# MapleIoT_P2_V1_0.net
KiCad netlist of a schematic drawn in EAGLE
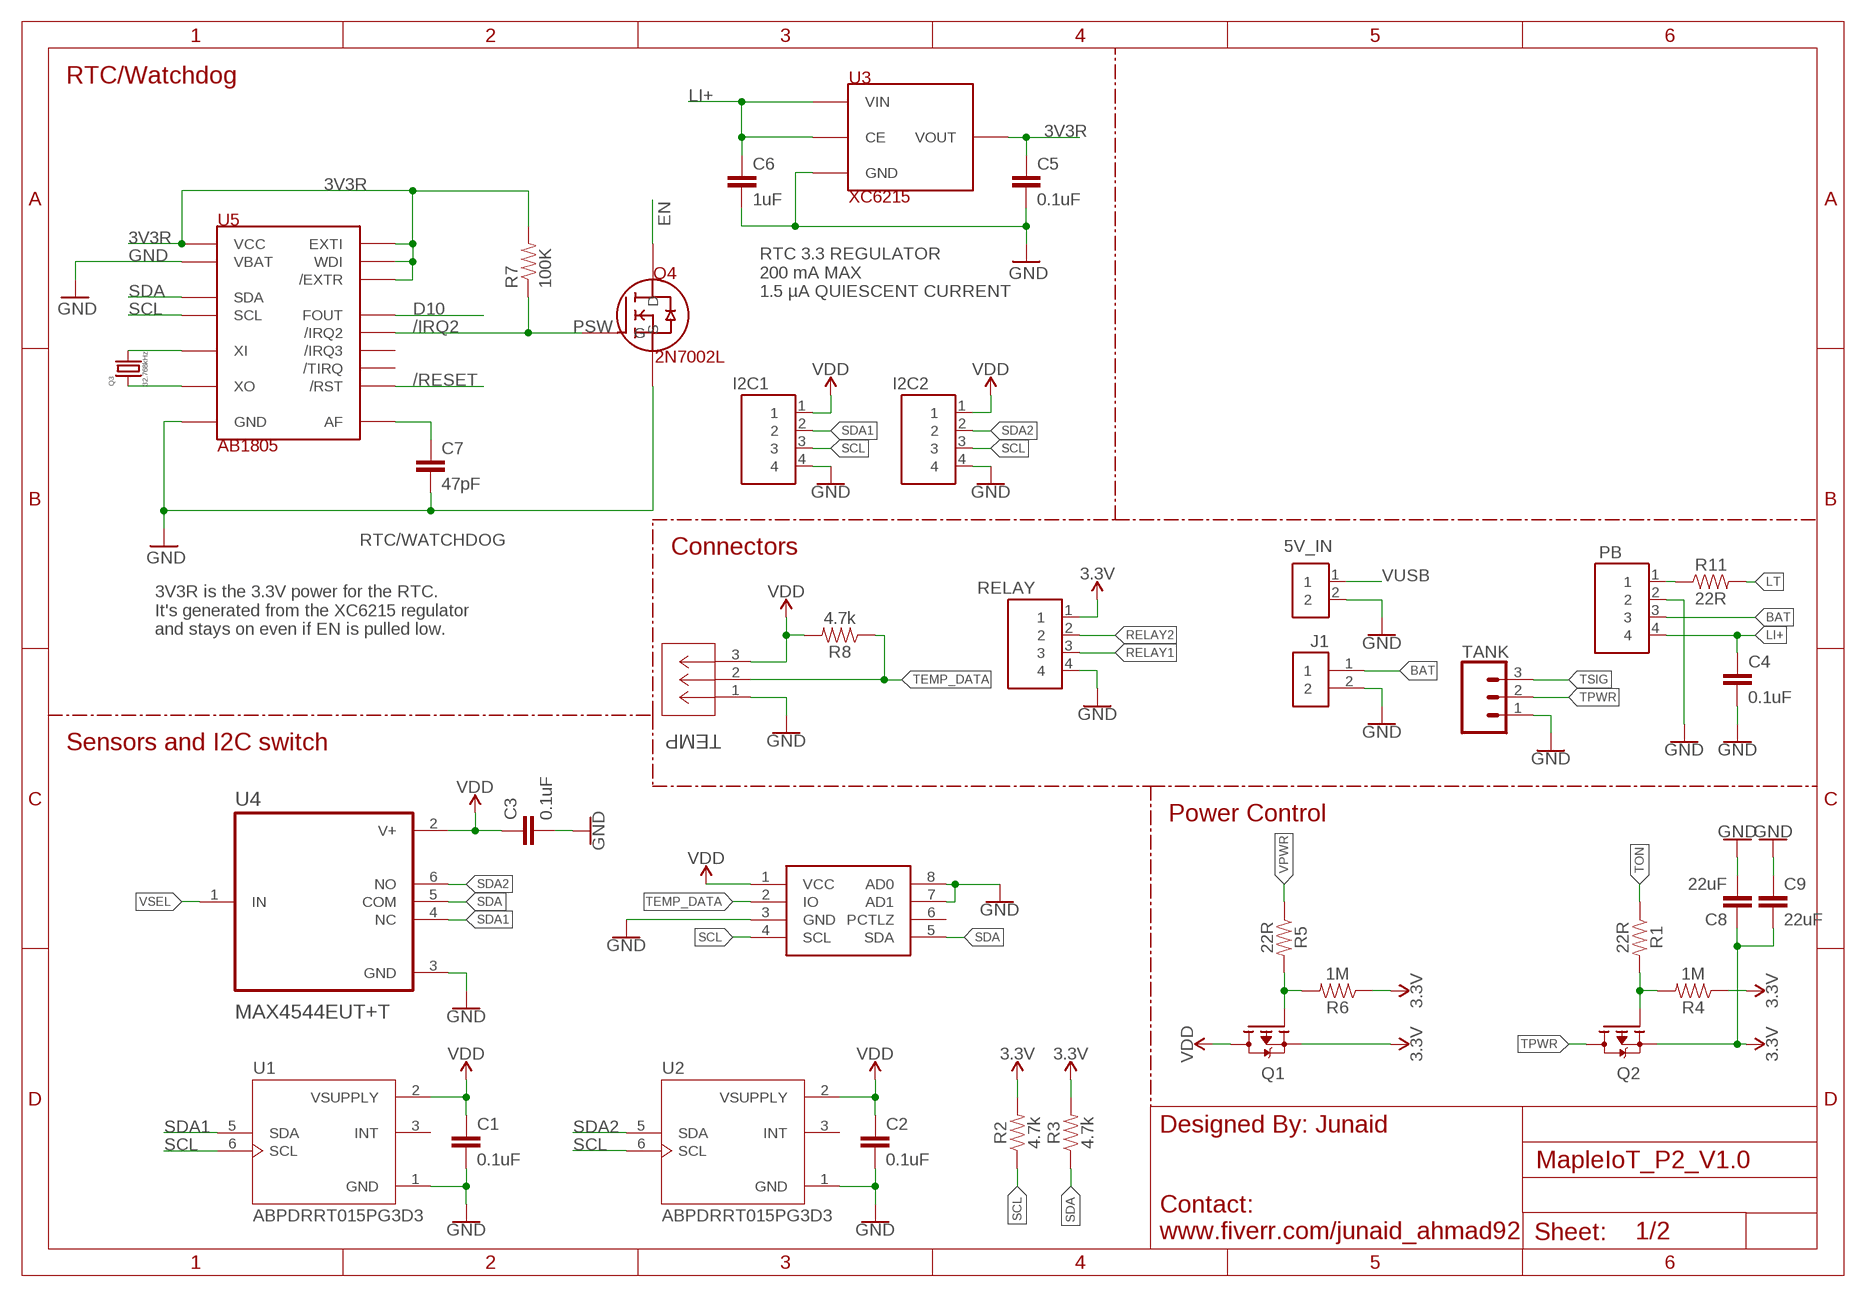
[diagram p0: schematic, sheet 1, part 1 of 2]
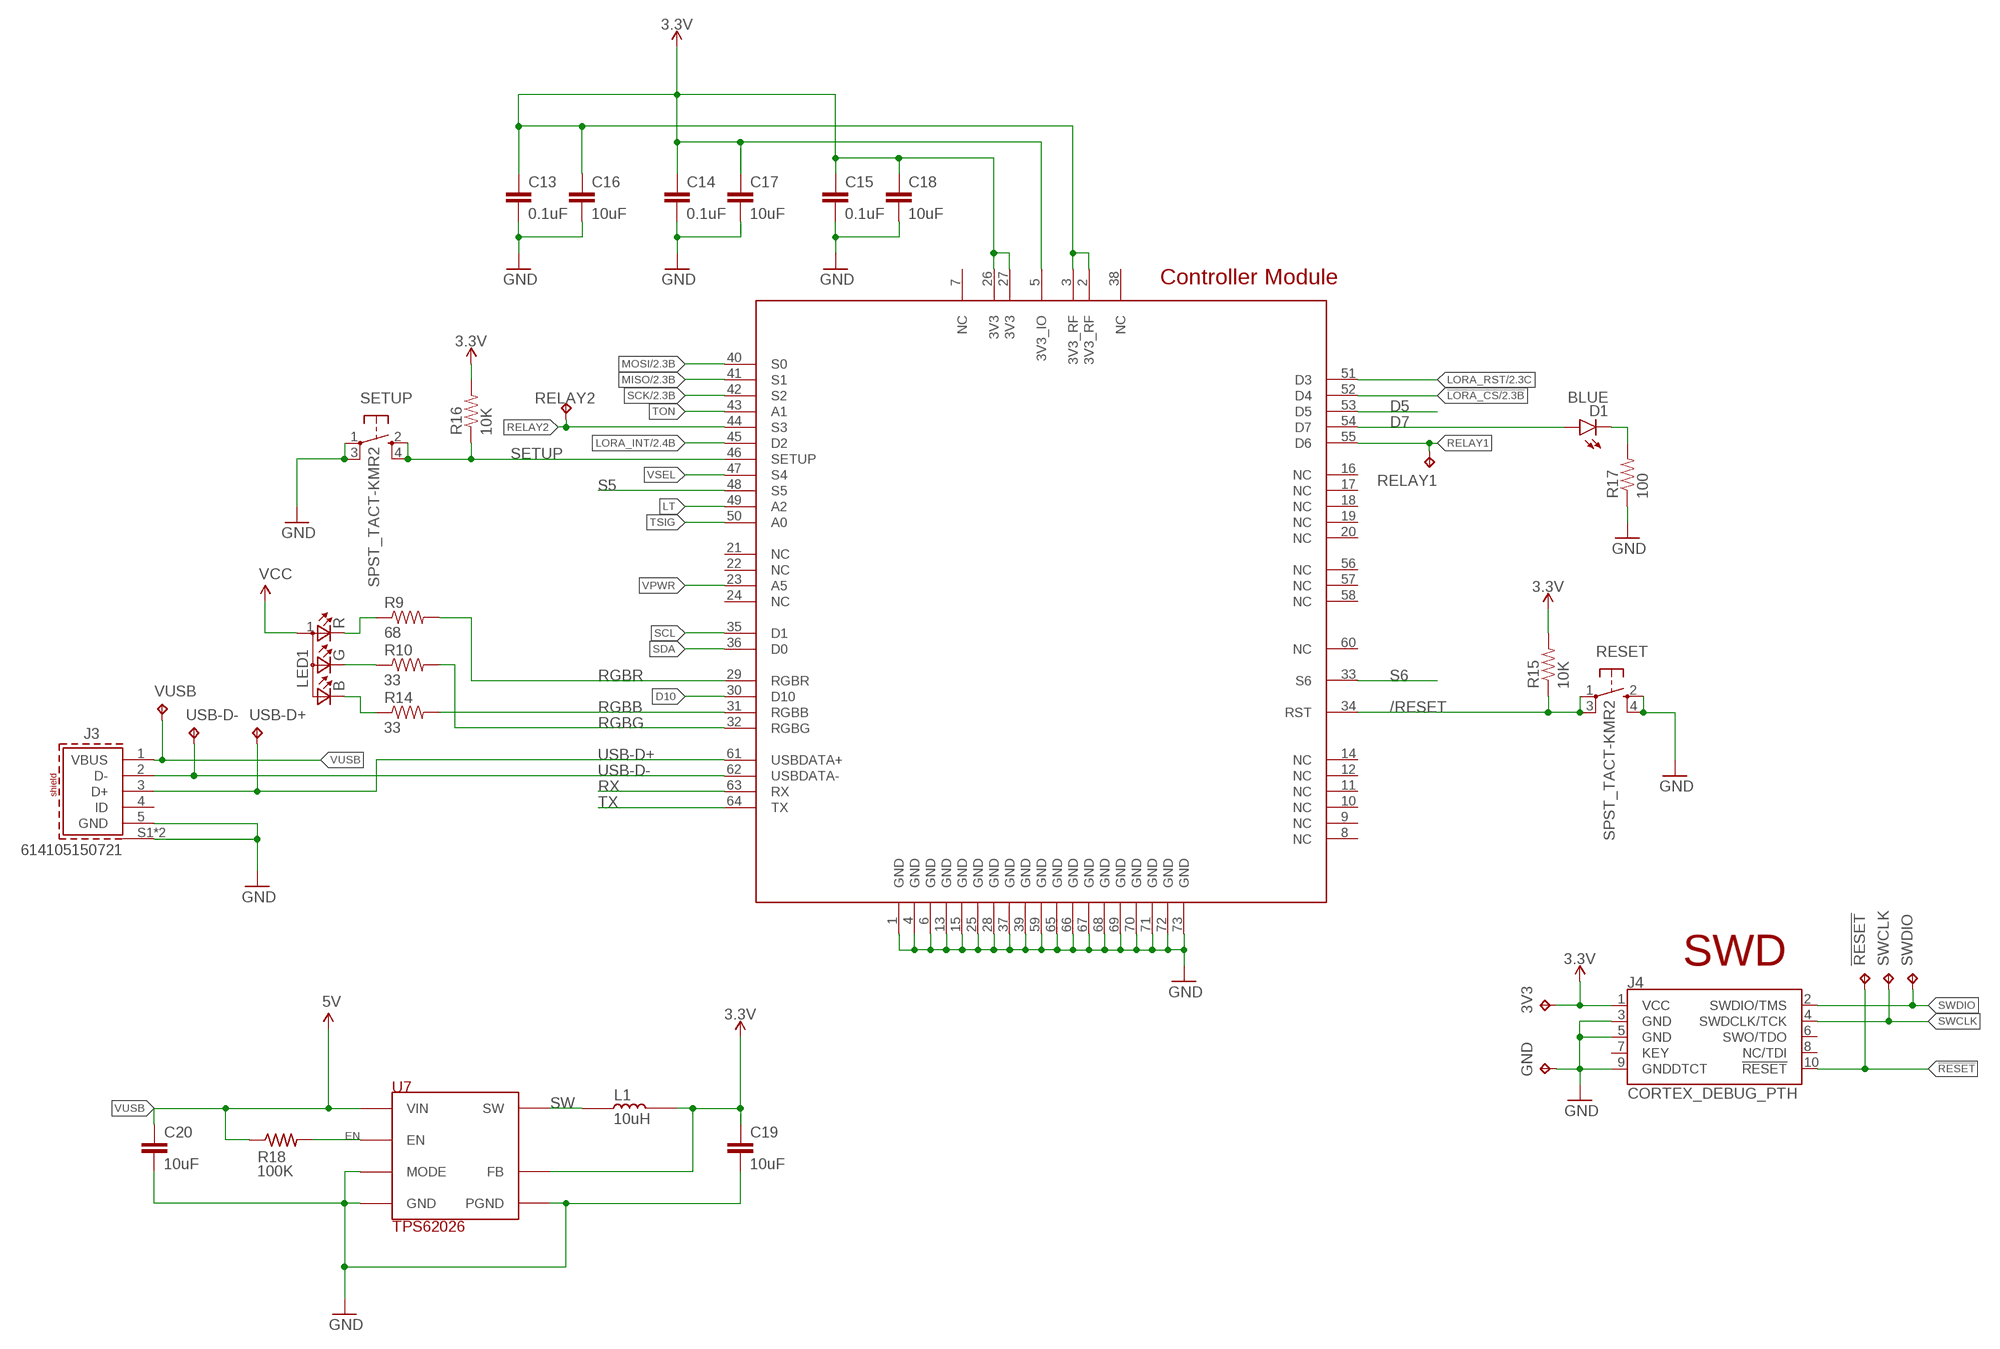
[diagram p1: schematic, sheet 1, part 2 of 2]
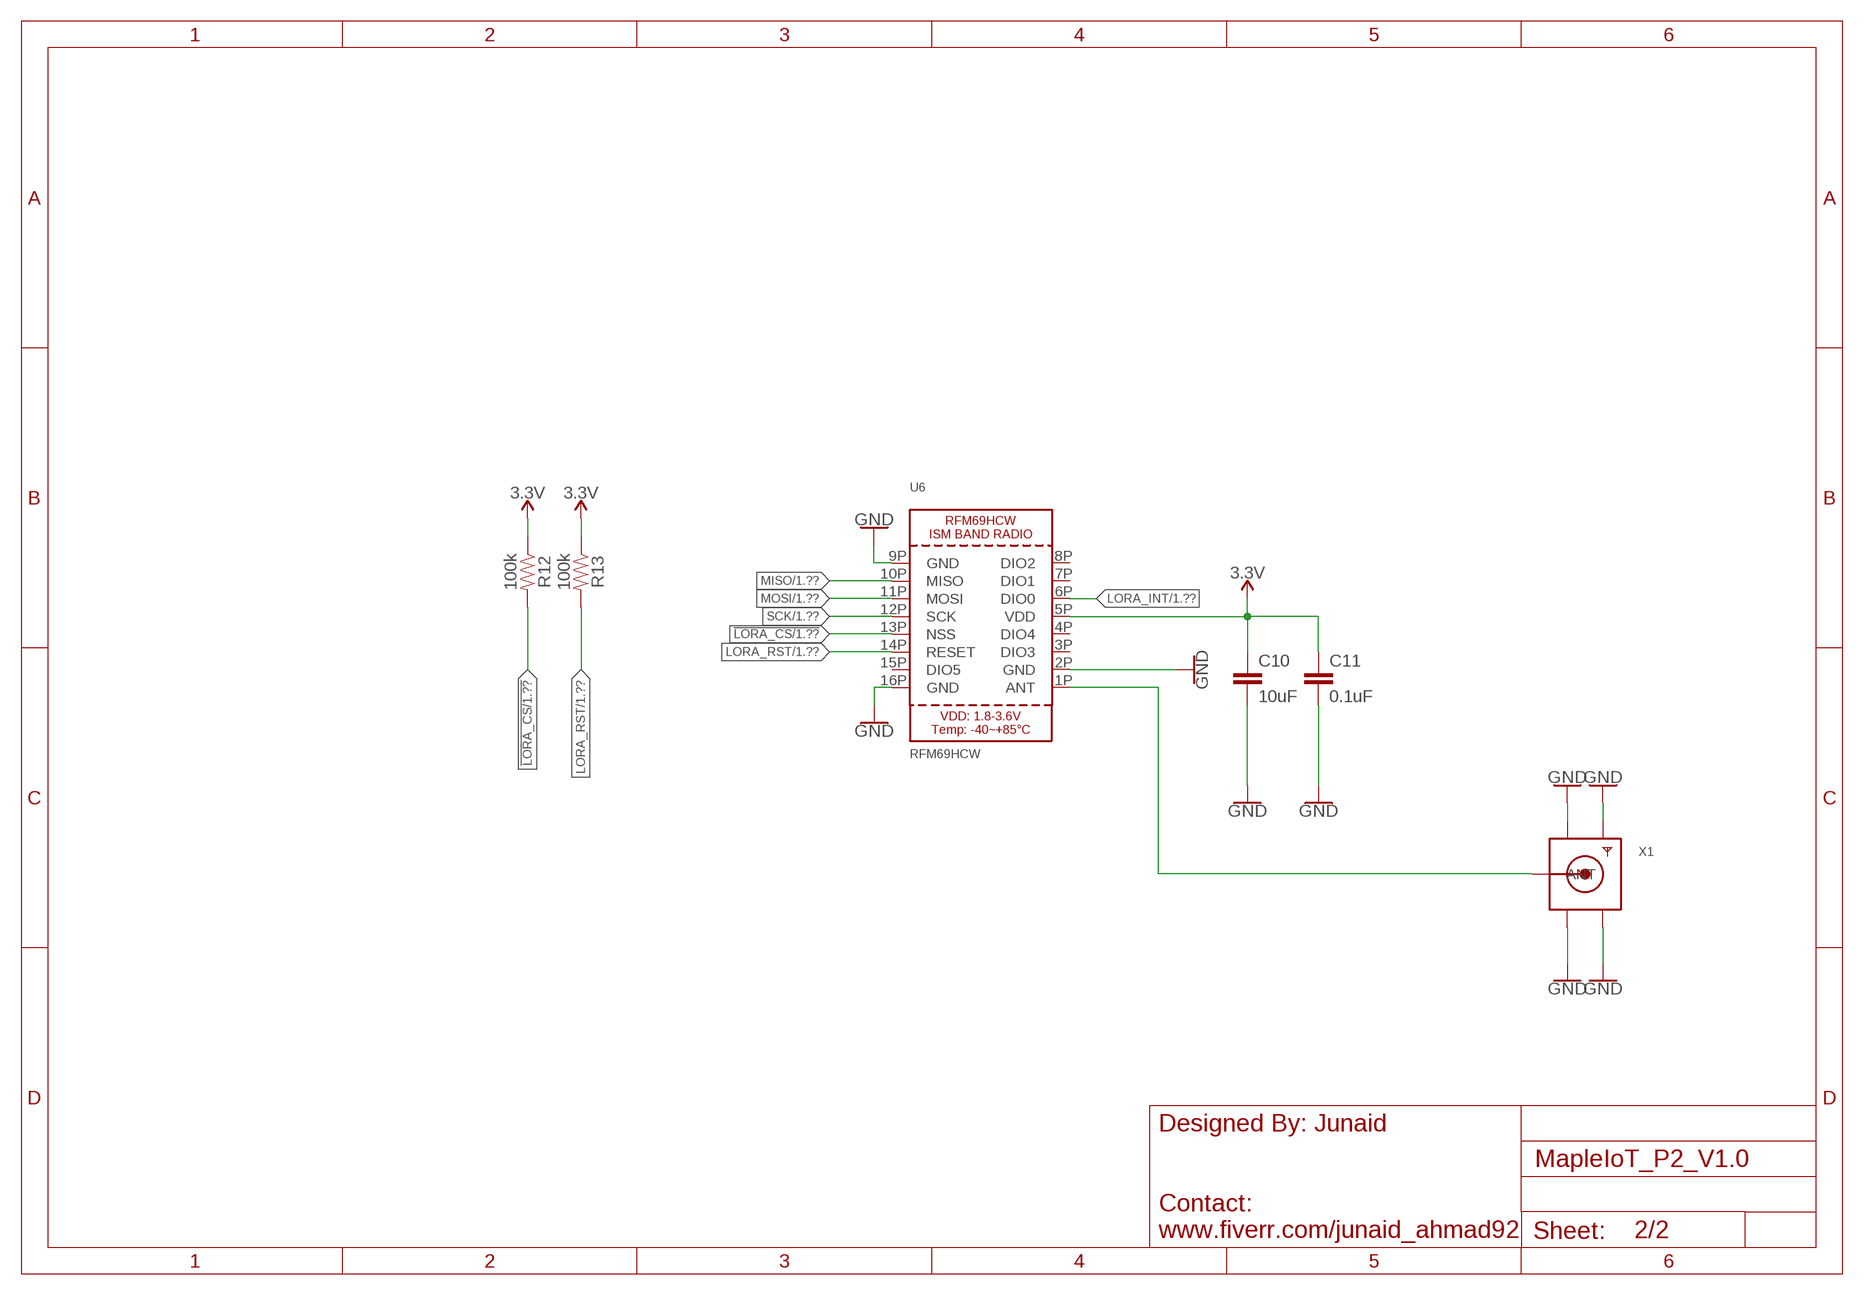
[diagram p2: schematic, sheet 2]

(export (version "E")
  (design (tool "Eeschema 10.0.6"))
  (components
    (comp (ref "!RESET")
      (value "TPTP15R")
      (footprint "eagle-import:TP15R")
      (libsource (lib "eagle-import") (part "TPTP15R"))
    )
    (comp (ref "3V3")
      (value "TPTP15R")
      (footprint "eagle-import:TP15R")
      (libsource (lib "eagle-import") (part "TPTP15R"))
    )
    (comp (ref "5V_IN")
      (value "B2B-XH-A(LF)(SN)")
      (footprint "eagle-import:SHDR2W64P0X250_1X2_740X575X700")
      (fields (field (name "RS_PART_NUMBER") "1667312"))
      (libsource (lib "eagle-import") (part "B2B-XH-A(LF)(SN)"))
    )
    (comp (ref "C1")
      (value "0.1uF")
      (footprint "eagle-import:C0603")
      (libsource (lib "eagle-import") (part "CAPACITORSC0603"))
    )
    (comp (ref "C2")
      (value "0.1uF")
      (footprint "eagle-import:C0603")
      (libsource (lib "eagle-import") (part "CAPACITORSC0603"))
    )
    (comp (ref "C3")
      (value "0.1uF")
      (footprint "eagle-import:C0603")
      (libsource (lib "eagle-import") (part "CAPACITORSC0603"))
    )
    (comp (ref "C4")
      (value "0.1uF")
      (footprint "eagle-import:C0603")
      (libsource (lib "eagle-import") (part "CAPACITORSC0603"))
    )
    (comp (ref "C5")
      (value "0.1uF")
      (footprint "eagle-import:0603-CAP")
      (libsource (lib "eagle-import") (part "CAP-0.1UF-0603"))
    )
    (comp (ref "C6")
      (value "1uF")
      (footprint "eagle-import:0603-CAP")
      (libsource (lib "eagle-import") (part "CAP-1UF-0603.DEV"))
    )
    (comp (ref "C7")
      (value "47pF")
      (footprint "eagle-import:0603-CAP")
      (libsource (lib "eagle-import") (part "CAP-47PF-0603"))
    )
    (comp (ref "C8")
      (value "22uF")
      (footprint "eagle-import:C1206")
      (libsource (lib "eagle-import") (part "CAPACITORSC1206"))
    )
    (comp (ref "C9")
      (value "22uF")
      (footprint "eagle-import:C1206")
      (libsource (lib "eagle-import") (part "CAPACITORSC1206"))
    )
    (comp (ref "C13")
      (value "0.1uF")
      (footprint "eagle-import:0603-CAP")
      (libsource (lib "eagle-import") (part "CAP-0.1UF-0603"))
    )
    (comp (ref "C14")
      (value "0.1uF")
      (footprint "eagle-import:0603-CAP")
      (libsource (lib "eagle-import") (part "CAP-0.1UF-0603"))
    )
    (comp (ref "C15")
      (value "0.1uF")
      (footprint "eagle-import:0603-CAP")
      (libsource (lib "eagle-import") (part "CAP-0.1UF-0603"))
    )
    (comp (ref "C16")
      (value "10uF")
      (footprint "eagle-import:0603-CAP")
      (libsource (lib "eagle-import") (part "CAP-10UF-0603"))
    )
    (comp (ref "C17")
      (value "10uF")
      (footprint "eagle-import:0603-CAP")
      (libsource (lib "eagle-import") (part "CAP-10UF-0603"))
    )
    (comp (ref "C18")
      (value "10uF")
      (footprint "eagle-import:0603-CAP")
      (libsource (lib "eagle-import") (part "CAP-10UF-0603"))
    )
    (comp (ref "C19")
      (value "10uF")
      (footprint "eagle-import:0603-CAP")
      (libsource (lib "eagle-import") (part "CAP-10UF-0603"))
    )
    (comp (ref "C20")
      (value "10uF")
      (footprint "eagle-import:0603-CAP")
      (libsource (lib "eagle-import") (part "CAP-10UF-0603"))
    )
    (comp (ref "D1")
      (value "BLUE")
      (footprint "eagle-import:LED-0603")
      (libsource (lib "eagle-import") (part "LED-BLUE0603"))
    )
    (comp (ref "GND")
      (value "TPTP15R")
      (footprint "eagle-import:TP15R")
      (libsource (lib "eagle-import") (part "TPTP15R"))
    )
    (comp (ref "I2C1")
      (value "B4B-XH-A(LF)(SN)")
      (footprint "eagle-import:SHDR4W64P0X250_1X4_1240X575X70")
      (fields (field (name "RS_PART_NUMBER") "8201551P"))
      (libsource (lib "eagle-import") (part "B4B-XH-A(LF)(SN)"))
    )
    (comp (ref "I2C2")
      (value "B4B-XH-A(LF)(SN)")
      (footprint "eagle-import:SHDR4W64P0X250_1X4_1240X575X70")
      (fields (field (name "RS_PART_NUMBER") "8201551P"))
      (libsource (lib "eagle-import") (part "B4B-XH-A(LF)(SN)"))
    )
    (comp (ref "J1")
      (value "B2B-PH-K-S(LF)(SN)")
      (footprint "eagle-import:JST_B2B-PH-K-S(LF)(SN)")
      (fields (field (name "DIGI-KEY_PART_NUMBER") "455-1704-ND") (field (name "MF") "JST Sales"))
      (libsource (lib "eagle-import") (part "B2B-PH-K-S(LF)(SN)"))
    )
    (comp (ref "J3")
      (value "614105150721")
      (footprint "eagle-import:614105150721")
      (libsource (lib "eagle-import") (part "614105150721"))
    )
    (comp (ref "J4")
      (value "CORTEX_DEBUG_PTH")
      (footprint "eagle-import:2X5-PTH-1.27MM")
      (libsource (lib "eagle-import") (part "CORTEX_DEBUG_PTH"))
    )
    (comp (ref "L1")
      (value "10uH")
      (footprint "eagle-import:BOURNS-INDUCTOR-3X3")
      (libsource (lib "eagle-import") (part "INDUCTOR-10UH"))
    )
    (comp (ref "LED1")
      (value "LED-RGB-CREE-SMD")
      (footprint "eagle-import:LED-RGB-CREE-SMD")
      (libsource (lib "eagle-import") (part "LED-RGB-CREE-SMD"))
    )
    (comp (ref "PB")
      (value "B4B-XH-A(LF)(SN)")
      (footprint "eagle-import:SHDR4W64P0X250_1X4_1240X575X70")
      (fields (field (name "RS_PART_NUMBER") "8201551P"))
      (libsource (lib "eagle-import") (part "B4B-XH-A(LF)(SN)"))
    )
    (comp (ref "Q1")
      (value "PMV65XP,215")
      (footprint "eagle-import:SOT95P230X110-3N")
      (fields (field (name "DIGI-KEY_PART_NUMBER") "1727-3124-1-ND") (field (name "MF") "Nexperia USA"))
      (libsource (lib "eagle-import") (part "PMV65XP,215"))
    )
    (comp (ref "Q2")
      (value "PMV65XP,215")
      (footprint "eagle-import:SOT95P230X110-3N")
      (fields (field (name "DIGI-KEY_PART_NUMBER") "1727-3124-1-ND") (field (name "MF") "Nexperia USA"))
      (libsource (lib "eagle-import") (part "PMV65XP,215"))
    )
    (comp (ref "Q3")
      (value "32.768kHz")
      (footprint "eagle-import:ABS07-120-CRYSTAL")
      (libsource (lib "eagle-import") (part "ABS07-120-32.768KHZ"))
    )
    (comp (ref "Q4")
      (value "2N7002L")
      (footprint "eagle-import:2N7002L")
      (libsource (lib "eagle-import") (part "2N7002L"))
    )
    (comp (ref "R1")
      (value "22R")
      (footprint "eagle-import:R0603")
      (libsource (lib "eagle-import") (part "RESISTORSR0603"))
    )
    (comp (ref "R2")
      (value "4.7k")
      (footprint "eagle-import:R0603")
      (libsource (lib "eagle-import") (part "RESISTORSR0603"))
    )
    (comp (ref "R3")
      (value "4.7k")
      (footprint "eagle-import:R0603")
      (libsource (lib "eagle-import") (part "RESISTORSR0603"))
    )
    (comp (ref "R4")
      (value "1M")
      (footprint "eagle-import:R0603")
      (libsource (lib "eagle-import") (part "RESISTORSR0603"))
    )
    (comp (ref "R5")
      (value "22R")
      (footprint "eagle-import:R0603")
      (libsource (lib "eagle-import") (part "RESISTORSR0603"))
    )
    (comp (ref "R6")
      (value "1M")
      (footprint "eagle-import:R0603")
      (libsource (lib "eagle-import") (part "RESISTORSR0603"))
    )
    (comp (ref "R7")
      (value "100K")
      (footprint "eagle-import:0603-RES")
      (libsource (lib "eagle-import") (part "RES-100K-0603"))
    )
    (comp (ref "R8")
      (value "4.7k")
      (footprint "eagle-import:R0603")
      (libsource (lib "eagle-import") (part "RESISTORSR0603"))
    )
    (comp (ref "R9")
      (value "68")
      (footprint "eagle-import:0603-RES")
      (libsource (lib "eagle-import") (part "RES-68-0603.DEV"))
    )
    (comp (ref "R10")
      (value "33")
      (footprint "eagle-import:0603-RES")
      (libsource (lib "eagle-import") (part "RES-33-0603.DEV"))
    )
    (comp (ref "R11")
      (value "22R")
      (footprint "eagle-import:R0603")
      (libsource (lib "eagle-import") (part "RESISTORSR0603"))
    )
    (comp (ref "R14")
      (value "33")
      (footprint "eagle-import:0603-RES")
      (libsource (lib "eagle-import") (part "RES-33-0603.DEV"))
    )
    (comp (ref "R15")
      (value "10K")
      (footprint "eagle-import:0603-RES")
      (libsource (lib "eagle-import") (part "RES-10K-06030603"))
    )
    (comp (ref "R16")
      (value "10K")
      (footprint "eagle-import:0603-RES")
      (libsource (lib "eagle-import") (part "RES-10K-06030603"))
    )
    (comp (ref "R17")
      (value "100")
      (footprint "eagle-import:0603-RES")
      (libsource (lib "eagle-import") (part "RES-100-0603.DEV"))
    )
    (comp (ref "R18")
      (value "100K")
      (footprint "eagle-import:R0603_P")
      (libsource (lib "eagle-import") (part "RES_0603100K_"))
    )
    (comp (ref "RELAY")
      (value "B4B-XH-A(LF)(SN)")
      (footprint "eagle-import:SHDR4W64P0X250_1X4_1240X575X70")
      (fields (field (name "RS_PART_NUMBER") "8201551P"))
      (libsource (lib "eagle-import") (part "B4B-XH-A(LF)(SN)"))
    )
    (comp (ref "RELAY1")
      (value "TPTP15R")
      (footprint "eagle-import:TP15R")
      (libsource (lib "eagle-import") (part "TPTP15R"))
    )
    (comp (ref "RELAY2")
      (value "TPTP15R")
      (footprint "eagle-import:TP15R")
      (libsource (lib "eagle-import") (part "TPTP15R"))
    )
    (comp (ref "RESET")
      (value "SPST_TACT-KMR2")
      (footprint "eagle-import:KMR2")
      (libsource (lib "eagle-import") (part "SPST_TACT-KMR2"))
    )
    (comp (ref "SETUP")
      (value "SPST_TACT-KMR2")
      (footprint "eagle-import:KMR2")
      (libsource (lib "eagle-import") (part "SPST_TACT-KMR2"))
    )
    (comp (ref "SWCLK")
      (value "TPTP15R")
      (footprint "eagle-import:TP15R")
      (libsource (lib "eagle-import") (part "TPTP15R"))
    )
    (comp (ref "SWDIO")
      (value "TPTP15R")
      (footprint "eagle-import:TP15R")
      (libsource (lib "eagle-import") (part "TPTP15R"))
    )
    (comp (ref "TANK")
      (value "B3B-XH-A(LF)(SN)")
      (footprint "eagle-import:SHDR3W64P0X250_1X3")
      (libsource (lib "eagle-import") (part "B3B-XH-A(LF)(SN)"))
    )
    (comp (ref "TEMP")
      (value "B3B-PH-K-S(LF)(SN)")
      (footprint "eagle-import:CONN_B3B-PH-K-S(LF)(SN)_JST")
      (fields (field (name "COPYRIGHT") "Copyright (C) 2018 Accelerated Designs. All rights reserved"))
      (libsource (lib "eagle-import") (part "B3B-PH-K-S(LF)(SN)"))
    )
    (comp (ref "U$2")
      (value "DS2482-100")
      (footprint "eagle-import:8-SOIC-MAXIM")
      (libsource (lib "eagle-import") (part "DS2482-100"))
    )
    (comp (ref "U$3") (value "P2") (footprint "eagle-import:P2") (libsource (lib "eagle-import") (part "P2")))
    (comp (ref "U1")
      (value "ABPDRRT015PG3D3")
      (footprint "eagle-import:XDCR_ABPDLNN100MG2A3")
      (fields
        (field (name "MF") "Honeywell Sensing")
        (field (name "MP") "ABPDLNN100MG2A3")
        (field (name "MP_1") "ABPDRRT015PG3D3")
      )
      (libsource (lib "eagle-import") (part "ABPDLNN100MG2A3"))
    )
    (comp (ref "U2")
      (value "ABPDRRT015PG3D3")
      (footprint "eagle-import:XDCR_ABPDLNN100MG2A3")
      (fields
        (field (name "MF") "Honeywell Sensing")
        (field (name "MP") "ABPDLNN100MG2A3")
        (field (name "MP_1") "ABPDRRT015PG3D3")
      )
      (libsource (lib "eagle-import") (part "ABPDLNN100MG2A3"))
    )
    (comp (ref "U3")
      (value "XC6215")
      (footprint "eagle-import:SOT-25-TOREX")
      (libsource (lib "eagle-import") (part "XC6215"))
    )
    (comp (ref "U4")
      (value "MAX4544EUT+T")
      (footprint "eagle-import:SOT95P280X145-6N")
      (fields
        (field (name "DIGI-KEY_PART_NUMBER") "MAX4544EUT+TCT-ND")
        (field (name "MF") "Maxim Integrated")
      )
      (libsource (lib "eagle-import") (part "MAX4544EUT+T"))
    )
    (comp (ref "U5")
      (value "AB1805")
      (footprint "eagle-import:16-VFQFN-ABRACON")
      (libsource (lib "eagle-import") (part "AB1805"))
    )
    (comp (ref "U7")
      (value "TPS62026")
      (footprint "eagle-import:10-HVSSOP-TI")
      (libsource (lib "eagle-import") (part "TPS62026-REG-3.3V"))
    )
    (comp (ref "USB-D+")
      (value "TPTP15R")
      (footprint "eagle-import:TP15R")
      (libsource (lib "eagle-import") (part "TPTP15R"))
    )
    (comp (ref "USB-D-")
      (value "TPTP15R")
      (footprint "eagle-import:TP15R")
      (libsource (lib "eagle-import") (part "TPTP15R"))
    )
    (comp (ref "VUSB")
      (value "TPTP15R")
      (footprint "eagle-import:TP15R")
      (libsource (lib "eagle-import") (part "TPTP15R"))
    )
    (comp (ref "C10")
      (value "10uF")
      (footprint "eagle-import:C0603")
      (libsource (lib "eagle-import") (part "CAPACITORSC0603"))
    )
    (comp (ref "C11")
      (value "0.1uF")
      (footprint "eagle-import:C0603")
      (libsource (lib "eagle-import") (part "CAPACITORSC0603"))
    )
    (comp (ref "R12")
      (value "100k")
      (footprint "eagle-import:R0603")
      (libsource (lib "eagle-import") (part "RESISTORSR0603"))
    )
    (comp (ref "R13")
      (value "100k")
      (footprint "eagle-import:R0603")
      (libsource (lib "eagle-import") (part "RESISTORSR0603"))
    )
    (comp (ref "U6")
      (value "RFM69HCW")
      (footprint "eagle-import:RFMHCW_SMT")
      (libsource (lib "eagle-import") (part "RFM69HCW_SMT"))
    )
    (comp (ref "X1")
      (value "SMACONNECTOR")
      (footprint "eagle-import:SMA90_DIP")
      (libsource (lib "eagle-import") (part "SMACONNECTOR"))
    )
  )
  (nets
    (net (code "1") (name "3.3V") (class "Default")
      (node (ref "3V3") (pin "TP") (pinfunction "TP_TP") (pintype "input"))
      (node (ref "C10") (pin "1") (pinfunction "1_1") (pintype "passive"))
      (node (ref "C11") (pin "1") (pinfunction "1_1") (pintype "passive"))
      (node (ref "C13") (pin "1") (pinfunction "1_1") (pintype "passive"))
      (node (ref "C14") (pin "1") (pinfunction "1_1") (pintype "passive"))
      (node (ref "C15") (pin "1") (pinfunction "1_1") (pintype "passive"))
      (node (ref "C16") (pin "1") (pinfunction "1_1") (pintype "passive"))
      (node (ref "C17") (pin "1") (pinfunction "1_1") (pintype "passive"))
      (node (ref "C18") (pin "1") (pinfunction "1_1") (pintype "passive"))
      (node (ref "C19") (pin "1") (pinfunction "1_1") (pintype "passive"))
      (node (ref "C8") (pin "1") (pinfunction "1_1") (pintype "passive"))
      (node (ref "C9") (pin "2") (pinfunction "2_2") (pintype "passive"))
      (node (ref "J4") (pin "1") (pinfunction "VCC_1") (pintype "bidirectional"))
      (node (ref "L1") (pin "2") (pinfunction "P$2_2") (pintype "passive"))
      (node (ref "Q1") (pin "2") (pinfunction "S_2") (pintype "passive"))
      (node (ref "Q2") (pin "2") (pinfunction "S_2") (pintype "passive"))
      (node (ref "R12") (pin "1") (pinfunction "1_1") (pintype "passive"))
      (node (ref "R13") (pin "1") (pinfunction "1_1") (pintype "passive"))
      (node (ref "R15") (pin "2") (pinfunction "2_2") (pintype "passive"))
      (node (ref "R16") (pin "2") (pinfunction "2_2") (pintype "passive"))
      (node (ref "R2") (pin "2") (pinfunction "2_2") (pintype "passive"))
      (node (ref "R3") (pin "2") (pinfunction "2_2") (pintype "passive"))
      (node (ref "R4") (pin "1") (pinfunction "1_1") (pintype "passive"))
      (node (ref "R6") (pin "1") (pinfunction "1_1") (pintype "passive"))
      (node (ref "RELAY") (pin "1") (pinfunction "1_1") (pintype "bidirectional"))
      (node (ref "U$3") (pin "2") (pinfunction "3V3_RF_2") (pintype "bidirectional"))
      (node (ref "U$3") (pin "26") (pinfunction "3V3_26") (pintype "bidirectional"))
      (node (ref "U$3") (pin "27") (pinfunction "3V3_27") (pintype "bidirectional"))
      (node (ref "U$3") (pin "3") (pinfunction "3V3_RF_3") (pintype "bidirectional"))
      (node (ref "U$3") (pin "5") (pinfunction "3V3_IO_5") (pintype "bidirectional"))
      (node (ref "U6") (pin "5P") (pinfunction "VDD_5P") (pintype "power_in"))
      (node (ref "U7") (pin "5") (pinfunction "FB_5") (pintype "passive"))
    )
    (net (code "2") (name "3V3R") (class "Default")
      (node (ref "C5") (pin "1") (pinfunction "1_1") (pintype "passive"))
      (node (ref "R7") (pin "2") (pinfunction "2_2") (pintype "passive"))
      (node (ref "U3") (pin "5") (pinfunction "VOUT_5") (pintype "passive"))
      (node (ref "U5") (pin "10") (pinfunction "EXTI_10") (pintype "input"))
      (node (ref "U5") (pin "13") (pinfunction "VCC_13") (pintype "passive"))
      (node (ref "U5") (pin "2") (pinfunction "WDI_2") (pintype "input"))
      (node (ref "U5") (pin "3") (pinfunction "/EXTR_3") (pintype "input"))
    )
    (net (code "3") (name "BAT") (class "Default")
      (node (ref "J1") (pin "1") (pinfunction "1_1") (pintype "passive"))
      (node (ref "PB") (pin "3") (pinfunction "3_3") (pintype "bidirectional"))
    )
    (net (code "4") (name "D5") (class "Default")
      (node (ref "U$3") (pin "53") (pinfunction "D5_53") (pintype "bidirectional"))
    )
    (net (code "5") (name "D7") (class "Default")
      (node (ref "D1") (pin "A") (pinfunction "A_A") (pintype "passive"))
      (node (ref "U$3") (pin "54") (pinfunction "D7_54") (pintype "bidirectional"))
    )
    (net (code "6") (name "D10") (class "Default")
      (node (ref "U$3") (pin "30") (pinfunction "D10_30") (pintype "bidirectional"))
      (node (ref "U5") (pin "11") (pinfunction "FOUT_11") (pintype "output"))
    )
    (net (code "7") (name "EN") (class "Default")
      (node (ref "Q4") (pin "3") (pinfunction "D_3") (pintype "bidirectional"))
      (node (ref "R18") (pin "2") (pinfunction "2_2") (pintype "passive"))
      (node (ref "U7") (pin "1") (pinfunction "EN_1") (pintype "input"))
    )
    (net (code "8") (name "GND") (class "Default")
      (node (ref "5V_IN") (pin "2") (pinfunction "2_2") (pintype "bidirectional"))
      (node (ref "C1") (pin "2") (pinfunction "2_2") (pintype "passive"))
      (node (ref "C10") (pin "2") (pinfunction "2_2") (pintype "passive"))
      (node (ref "C11") (pin "2") (pinfunction "2_2") (pintype "passive"))
      (node (ref "C13") (pin "2") (pinfunction "2_2") (pintype "passive"))
      (node (ref "C14") (pin "2") (pinfunction "2_2") (pintype "passive"))
      (node (ref "C15") (pin "2") (pinfunction "2_2") (pintype "passive"))
      (node (ref "C16") (pin "2") (pinfunction "2_2") (pintype "passive"))
      (node (ref "C17") (pin "2") (pinfunction "2_2") (pintype "passive"))
      (node (ref "C18") (pin "2") (pinfunction "2_2") (pintype "passive"))
      (node (ref "C19") (pin "2") (pinfunction "2_2") (pintype "passive"))
      (node (ref "C2") (pin "2") (pinfunction "2_2") (pintype "passive"))
      (node (ref "C20") (pin "2") (pinfunction "2_2") (pintype "passive"))
      (node (ref "C3") (pin "2") (pinfunction "2_2") (pintype "passive"))
      (node (ref "C4") (pin "2") (pinfunction "2_2") (pintype "passive"))
      (node (ref "C5") (pin "2") (pinfunction "2_2") (pintype "passive"))
      (node (ref "C6") (pin "2") (pinfunction "2_2") (pintype "passive"))
      (node (ref "C7") (pin "2") (pinfunction "2_2") (pintype "passive"))
      (node (ref "C8") (pin "2") (pinfunction "2_2") (pintype "passive"))
      (node (ref "C9") (pin "1") (pinfunction "1_1") (pintype "passive"))
      (node (ref "GND") (pin "TP") (pinfunction "TP_TP") (pintype "input"))
      (node (ref "I2C1") (pin "4") (pinfunction "4_4") (pintype "bidirectional"))
      (node (ref "I2C2") (pin "4") (pinfunction "4_4") (pintype "bidirectional"))
      (node (ref "J1") (pin "2") (pinfunction "2_2") (pintype "passive"))
      (node (ref "J3") (pin "5") (pinfunction "GND_5") (pintype "passive"))
      (node (ref "J3") (pin "S1") (pinfunction "SHIELD_S1") (pintype "passive"))
      (node (ref "J3") (pin "S2") (pinfunction "SHIELD_S2") (pintype "passive"))
      (node (ref "J4") (pin "3") (pinfunction "GND_3") (pintype "bidirectional"))
      (node (ref "J4") (pin "5") (pinfunction "GND_5") (pintype "bidirectional"))
      (node (ref "J4") (pin "9") (pinfunction "GNDDTCT_9") (pintype "bidirectional"))
      (node (ref "PB") (pin "2") (pinfunction "2_2") (pintype "bidirectional"))
      (node (ref "Q4") (pin "2") (pinfunction "S_2") (pintype "bidirectional"))
      (node (ref "R17") (pin "1") (pinfunction "1_1") (pintype "passive"))
      (node (ref "RELAY") (pin "4") (pinfunction "4_4") (pintype "bidirectional"))
      (node (ref "RESET") (pin "2") (pinfunction "S_2") (pintype "passive"))
      (node (ref "RESET") (pin "4") (pinfunction "S1_4") (pintype "passive"))
      (node (ref "SETUP") (pin "1") (pinfunction "P_1") (pintype "passive"))
      (node (ref "SETUP") (pin "3") (pinfunction "P1_3") (pintype "passive"))
      (node (ref "TANK") (pin "1") (pinfunction "1_1") (pintype "passive"))
      (node (ref "TEMP") (pin "1") (pinfunction "1_1") (pintype "passive"))
      (node (ref "U$2") (pin "3") (pinfunction "GND_3") (pintype "power_in"))
      (node (ref "U$2") (pin "7") (pinfunction "AD1_7") (pintype "input"))
      (node (ref "U$2") (pin "8") (pinfunction "AD0_8") (pintype "input"))
      (node (ref "U$3") (pin "1") (pinfunction "GND_1") (pintype "bidirectional"))
      (node (ref "U$3") (pin "13") (pinfunction "GND_13") (pintype "bidirectional"))
      (node (ref "U$3") (pin "15") (pinfunction "GND_15") (pintype "bidirectional"))
      (node (ref "U$3") (pin "25") (pinfunction "GND_25") (pintype "bidirectional"))
      (node (ref "U$3") (pin "28") (pinfunction "GND_28") (pintype "bidirectional"))
      (node (ref "U$3") (pin "37") (pinfunction "GND_37") (pintype "bidirectional"))
      (node (ref "U$3") (pin "39") (pinfunction "GND_39") (pintype "bidirectional"))
      (node (ref "U$3") (pin "4") (pinfunction "GND_4") (pintype "bidirectional"))
      (node (ref "U$3") (pin "59") (pinfunction "GND_59") (pintype "bidirectional"))
      (node (ref "U$3") (pin "6") (pinfunction "GND_6") (pintype "bidirectional"))
      (node (ref "U$3") (pin "65") (pinfunction "GND_65") (pintype "bidirectional"))
      (node (ref "U$3") (pin "66") (pinfunction "GND_66") (pintype "bidirectional"))
      (node (ref "U$3") (pin "67") (pinfunction "GND_67") (pintype "bidirectional"))
      (node (ref "U$3") (pin "68") (pinfunction "GND_68") (pintype "bidirectional"))
      (node (ref "U$3") (pin "69") (pinfunction "GND_69") (pintype "bidirectional"))
      (node (ref "U$3") (pin "70") (pinfunction "GND_70") (pintype "bidirectional"))
      (node (ref "U$3") (pin "71") (pinfunction "GND_71") (pintype "bidirectional"))
      (node (ref "U$3") (pin "72") (pinfunction "GND_72") (pintype "bidirectional"))
      (node (ref "U$3") (pin "73") (pinfunction "GND_73") (pintype "bidirectional"))
      (node (ref "U1") (pin "1") (pinfunction "GND_1") (pintype "power_in"))
      (node (ref "U2") (pin "1") (pinfunction "GND_1") (pintype "power_in"))
      (node (ref "U3") (pin "2") (pinfunction "GND_2") (pintype "passive"))
      (node (ref "U4") (pin "3") (pinfunction "GND_3") (pintype "power_in"))
      (node (ref "U5") (pin "5") (pinfunction "VBAT_5") (pintype "passive"))
      (node (ref "U5") (pin "9") (pinfunction "GND_9") (pintype "passive"))
      (node (ref "U5") (pin "EP") (pinfunction "GND_EP") (pintype "passive"))
      (node (ref "U6") (pin "16P") (pinfunction "GND_16P") (pintype "power_in"))
      (node (ref "U6") (pin "2P") (pinfunction "GND_2P") (pintype "power_in"))
      (node (ref "U6") (pin "9P") (pinfunction "GND_9P") (pintype "power_in"))
      (node (ref "U7") (pin "10") (pinfunction "PGND_10") (pintype "passive"))
      (node (ref "U7") (pin "4") (pinfunction "GND_4") (pintype "passive"))
      (node (ref "U7") (pin "6") (pinfunction "MODE_6") (pintype "input"))
      (node (ref "U7") (pin "9") (pinfunction "PGND_9") (pintype "passive"))
      (node (ref "U7") (pin "P") (pinfunction "GND_P") (pintype "passive"))
      (node (ref "X1") (pin "GND1") (pinfunction "GND1_GND1") (pintype "power_in"))
      (node (ref "X1") (pin "GND2") (pinfunction "GND2_GND2") (pintype "power_in"))
      (node (ref "X1") (pin "GND3") (pinfunction "GND3_GND3") (pintype "power_in"))
      (node (ref "X1") (pin "GND4") (pinfunction "GND4_GND4") (pintype "power_in"))
    )
    (net (code "9") (name "LI+") (class "Default")
      (node (ref "C4") (pin "1") (pinfunction "1_1") (pintype "passive"))
      (node (ref "C6") (pin "1") (pinfunction "1_1") (pintype "passive"))
      (node (ref "PB") (pin "4") (pinfunction "4_4") (pintype "bidirectional"))
      (node (ref "U3") (pin "1") (pinfunction "VIN_1") (pintype "passive"))
      (node (ref "U3") (pin "3") (pinfunction "CE_3") (pintype "input"))
    )
    (net (code "10") (name "LORA_INT") (class "Default")
      (node (ref "U$3") (pin "45") (pinfunction "D2_45") (pintype "bidirectional"))
      (node (ref "U6") (pin "6P") (pinfunction "DIO0_6P") (pintype "bidirectional"))
    )
    (net (code "11") (name "LORA_RST") (class "Default")
      (node (ref "R13") (pin "2") (pinfunction "2_2") (pintype "passive"))
      (node (ref "U$3") (pin "51") (pinfunction "D3_51") (pintype "bidirectional"))
      (node (ref "U6") (pin "14P") (pinfunction "RESET_14P") (pintype "input"))
    )
    (net (code "12") (name "LT") (class "Default")
      (node (ref "R11") (pin "2") (pinfunction "2_2") (pintype "passive"))
      (node (ref "U$3") (pin "49") (pinfunction "A2_49") (pintype "bidirectional"))
    )
    (net (code "13") (name "MISO") (class "Default")
      (node (ref "U$3") (pin "41") (pinfunction "S1_41") (pintype "bidirectional"))
      (node (ref "U6") (pin "10P") (pinfunction "MISO_10P") (pintype "output"))
    )
    (net (code "14") (name "MOSI") (class "Default")
      (node (ref "U$3") (pin "40") (pinfunction "S0_40") (pintype "bidirectional"))
      (node (ref "U6") (pin "11P") (pinfunction "MOSI_11P") (pintype "input"))
    )
    (net (code "15") (name "Net-(D1-PadC)") (class "Default")
      (node (ref "D1") (pin "C") (pinfunction "C_C") (pintype "passive"))
      (node (ref "R17") (pin "2") (pinfunction "2_2") (pintype "passive"))
    )
    (net (code "16") (name "Net-(LED1-B)") (class "Default")
      (node (ref "LED1") (pin "2") (pinfunction "B_2") (pintype "passive"))
      (node (ref "R14") (pin "1") (pinfunction "1_1") (pintype "passive"))
    )
    (net (code "17") (name "Net-(LED1-G)") (class "Default")
      (node (ref "LED1") (pin "3") (pinfunction "G_3") (pintype "passive"))
      (node (ref "R10") (pin "1") (pinfunction "1_1") (pintype "passive"))
    )
    (net (code "18") (name "Net-(LED1-R)") (class "Default")
      (node (ref "LED1") (pin "4") (pinfunction "R_4") (pintype "passive"))
      (node (ref "R9") (pin "1") (pinfunction "1_1") (pintype "passive"))
    )
    (net (code "19") (name "Net-(PB-Pad1)") (class "Default")
      (node (ref "PB") (pin "1") (pinfunction "1_1") (pintype "bidirectional"))
      (node (ref "R11") (pin "1") (pinfunction "1_1") (pintype "passive"))
    )
    (net (code "20") (name "Net-(Q1-G)") (class "Default")
      (node (ref "Q1") (pin "1") (pinfunction "G_1") (pintype "passive"))
      (node (ref "R5") (pin "2") (pinfunction "2_2") (pintype "passive"))
      (node (ref "R6") (pin "2") (pinfunction "2_2") (pintype "passive"))
    )
    (net (code "21") (name "Net-(Q2-G)") (class "Default")
      (node (ref "Q2") (pin "1") (pinfunction "G_1") (pintype "passive"))
      (node (ref "R1") (pin "2") (pinfunction "2_2") (pintype "passive"))
      (node (ref "R4") (pin "2") (pinfunction "2_2") (pintype "passive"))
    )
    (net (code "22") (name "Net-(U5-AF)") (class "Default")
      (node (ref "C7") (pin "1") (pinfunction "1_1") (pintype "passive"))
      (node (ref "U5") (pin "14") (pinfunction "AF_14") (pintype "output"))
    )
    (net (code "23") (name "Net-(U5-XI)") (class "Default")
      (node (ref "Q3") (pin "2") (pinfunction "2_2") (pintype "passive"))
      (node (ref "U5") (pin "16") (pinfunction "XI_16") (pintype "bidirectional"))
    )
    (net (code "24") (name "Net-(U5-XO)") (class "Default")
      (node (ref "Q3") (pin "1") (pinfunction "1_1") (pintype "passive"))
      (node (ref "U5") (pin "15") (pinfunction "XO_15") (pintype "bidirectional"))
    )
    (net (code "25") (name "Net-(U6-ANT)") (class "Default")
      (node (ref "U6") (pin "1P") (pinfunction "ANT_1P") (pintype "bidirectional"))
      (node (ref "X1") (pin "ANTENNA") (pinfunction "ANT_ANTENNA") (pintype "bidirectional"))
    )
    (net (code "26") (name "RELAY1") (class "Default")
      (node (ref "RELAY") (pin "3") (pinfunction "3_3") (pintype "bidirectional"))
      (node (ref "RELAY1") (pin "TP") (pinfunction "TP_TP") (pintype "input"))
      (node (ref "U$3") (pin "55") (pinfunction "D6_55") (pintype "bidirectional"))
    )
    (net (code "27") (name "RELAY2") (class "Default")
      (node (ref "RELAY") (pin "2") (pinfunction "2_2") (pintype "bidirectional"))
      (node (ref "RELAY2") (pin "TP") (pinfunction "TP_TP") (pintype "input"))
      (node (ref "U$3") (pin "44") (pinfunction "S3_44") (pintype "bidirectional"))
    )
    (net (code "28") (name "RGBB") (class "Default")
      (node (ref "R14") (pin "2") (pinfunction "2_2") (pintype "passive"))
      (node (ref "U$3") (pin "31") (pinfunction "RGBB_31") (pintype "bidirectional"))
    )
    (net (code "29") (name "RGBG") (class "Default")
      (node (ref "R10") (pin "2") (pinfunction "2_2") (pintype "passive"))
      (node (ref "U$3") (pin "32") (pinfunction "RGBG_32") (pintype "bidirectional"))
    )
    (net (code "30") (name "RGBR") (class "Default")
      (node (ref "R9") (pin "2") (pinfunction "2_2") (pintype "passive"))
      (node (ref "U$3") (pin "29") (pinfunction "RGBR_29") (pintype "bidirectional"))
    )
    (net (code "31") (name "RX") (class "Default")
      (node (ref "U$3") (pin "63") (pinfunction "RX_63") (pintype "bidirectional"))
    )
    (net (code "32") (name "S5") (class "Default")
      (node (ref "U$3") (pin "48") (pinfunction "S5_48") (pintype "bidirectional"))
    )
    (net (code "33") (name "S6") (class "Default")
      (node (ref "U$3") (pin "33") (pinfunction "S6_33") (pintype "bidirectional"))
    )
    (net (code "34") (name "SCK") (class "Default")
      (node (ref "U$3") (pin "42") (pinfunction "S2_42") (pintype "bidirectional"))
      (node (ref "U6") (pin "12P") (pinfunction "SCK_12P") (pintype "input"))
    )
    (net (code "35") (name "SCL") (class "Default")
      (node (ref "I2C1") (pin "3") (pinfunction "3_3") (pintype "bidirectional"))
      (node (ref "I2C2") (pin "3") (pinfunction "3_3") (pintype "bidirectional"))
      (node (ref "R2") (pin "1") (pinfunction "1_1") (pintype "passive"))
      (node (ref "U$2") (pin "4") (pinfunction "SCL_4") (pintype "bidirectional"))
      (node (ref "U$3") (pin "35") (pinfunction "D1_35") (pintype "bidirectional"))
      (node (ref "U1") (pin "6") (pinfunction "SCL_6") (pintype "input"))
      (node (ref "U2") (pin "6") (pinfunction "SCL_6") (pintype "input"))
      (node (ref "U5") (pin "7") (pinfunction "SCL_7") (pintype "bidirectional"))
    )
    (net (code "36") (name "SDA") (class "Default")
      (node (ref "R3") (pin "1") (pinfunction "1_1") (pintype "passive"))
      (node (ref "U$2") (pin "5") (pinfunction "SDA_5") (pintype "bidirectional"))
      (node (ref "U$3") (pin "36") (pinfunction "D0_36") (pintype "bidirectional"))
      (node (ref "U4") (pin "5") (pinfunction "COM_5") (pintype "output"))
      (node (ref "U5") (pin "6") (pinfunction "SDA_6") (pintype "bidirectional"))
    )
    (net (code "37") (name "SDA1") (class "Default")
      (node (ref "I2C1") (pin "2") (pinfunction "2_2") (pintype "bidirectional"))
      (node (ref "U1") (pin "5") (pinfunction "SDA_5") (pintype "bidirectional"))
      (node (ref "U4") (pin "4") (pinfunction "NC_4") (pintype "bidirectional"))
    )
    (net (code "38") (name "SDA2") (class "Default")
      (node (ref "I2C2") (pin "2") (pinfunction "2_2") (pintype "bidirectional"))
      (node (ref "U2") (pin "5") (pinfunction "SDA_5") (pintype "bidirectional"))
      (node (ref "U4") (pin "6") (pinfunction "NO_6") (pintype "input"))
    )
    (net (code "39") (name "SETUP") (class "Default")
      (node (ref "R16") (pin "1") (pinfunction "1_1") (pintype "passive"))
      (node (ref "SETUP") (pin "2") (pinfunction "S_2") (pintype "passive"))
      (node (ref "SETUP") (pin "4") (pinfunction "S1_4") (pintype "passive"))
      (node (ref "U$3") (pin "46") (pinfunction "SETUP_46") (pintype "bidirectional"))
    )
    (net (code "40") (name "SW") (class "Default")
      (node (ref "L1") (pin "1") (pinfunction "P$1_1") (pintype "passive"))
      (node (ref "U7") (pin "7") (pinfunction "SW_7") (pintype "passive"))
      (node (ref "U7") (pin "8") (pinfunction "SW_8") (pintype "passive"))
    )
    (net (code "41") (name "SWCLK") (class "Default")
      (node (ref "J4") (pin "4") (pinfunction "SWDCLK/TCK_4") (pintype "bidirectional"))
      (node (ref "SWCLK") (pin "TP") (pinfunction "TP_TP") (pintype "input"))
    )
    (net (code "42") (name "SWDIO") (class "Default")
      (node (ref "J4") (pin "2") (pinfunction "SWDIO/TMS_2") (pintype "bidirectional"))
      (node (ref "SWDIO") (pin "TP") (pinfunction "TP_TP") (pintype "input"))
    )
    (net (code "43") (name "TEMP_DATA") (class "Default")
      (node (ref "R8") (pin "1") (pinfunction "1_1") (pintype "passive"))
      (node (ref "TEMP") (pin "2") (pinfunction "2_2") (pintype "passive"))
      (node (ref "U$2") (pin "2") (pinfunction "IO_2") (pintype "bidirectional"))
    )
    (net (code "44") (name "TON") (class "Default")
      (node (ref "R1") (pin "1") (pinfunction "1_1") (pintype "passive"))
      (node (ref "U$3") (pin "43") (pinfunction "A1_43") (pintype "bidirectional"))
    )
    (net (code "45") (name "TPWR") (class "Default")
      (node (ref "Q2") (pin "3") (pinfunction "D_3") (pintype "passive"))
      (node (ref "TANK") (pin "2") (pinfunction "2_2") (pintype "passive"))
    )
    (net (code "46") (name "TSIG") (class "Default")
      (node (ref "TANK") (pin "3") (pinfunction "3_3") (pintype "passive"))
      (node (ref "U$3") (pin "50") (pinfunction "A0_50") (pintype "bidirectional"))
    )
    (net (code "47") (name "TX") (class "Default")
      (node (ref "U$3") (pin "64") (pinfunction "TX_64") (pintype "bidirectional"))
    )
    (net (code "48") (name "USB-D+") (class "Default")
      (node (ref "J3") (pin "3") (pinfunction "D+_3") (pintype "passive"))
      (node (ref "U$3") (pin "61") (pinfunction "USBDATA+_61") (pintype "bidirectional"))
      (node (ref "USB-D+") (pin "TP") (pinfunction "TP_TP") (pintype "input"))
    )
    (net (code "49") (name "USB-D-") (class "Default")
      (node (ref "J3") (pin "2") (pinfunction "D-_2") (pintype "passive"))
      (node (ref "U$3") (pin "62") (pinfunction "USBDATA-_62") (pintype "bidirectional"))
      (node (ref "USB-D-") (pin "TP") (pinfunction "TP_TP") (pintype "input"))
    )
    (net (code "50") (name "VCC") (class "Default")
      (node (ref "LED1") (pin "1") (pinfunction "A_1") (pintype "passive"))
    )
    (net (code "51") (name "VDD") (class "Default")
      (node (ref "C1") (pin "1") (pinfunction "1_1") (pintype "passive"))
      (node (ref "C2") (pin "1") (pinfunction "1_1") (pintype "passive"))
      (node (ref "C3") (pin "1") (pinfunction "1_1") (pintype "passive"))
      (node (ref "I2C1") (pin "1") (pinfunction "1_1") (pintype "bidirectional"))
      (node (ref "I2C2") (pin "1") (pinfunction "1_1") (pintype "bidirectional"))
      (node (ref "Q1") (pin "3") (pinfunction "D_3") (pintype "passive"))
      (node (ref "R8") (pin "2") (pinfunction "2_2") (pintype "passive"))
      (node (ref "TEMP") (pin "3") (pinfunction "3_3") (pintype "passive"))
      (node (ref "U$2") (pin "1") (pinfunction "VCC_1") (pintype "power_in"))
      (node (ref "U1") (pin "2") (pinfunction "VSUPPLY_2") (pintype "power_in"))
      (node (ref "U2") (pin "2") (pinfunction "VSUPPLY_2") (pintype "power_in"))
      (node (ref "U4") (pin "2") (pinfunction "V+_2") (pintype "power_in"))
    )
    (net (code "52") (name "VPWR") (class "Default")
      (node (ref "R5") (pin "1") (pinfunction "1_1") (pintype "passive"))
      (node (ref "U$3") (pin "23") (pinfunction "A5_23") (pintype "bidirectional"))
    )
    (net (code "53") (name "VSEL") (class "Default")
      (node (ref "U$3") (pin "47") (pinfunction "S4_47") (pintype "bidirectional"))
      (node (ref "U4") (pin "1") (pinfunction "IN_1") (pintype "input"))
    )
    (net (code "54") (name "VUSB") (class "Default")
      (node (ref "5V_IN") (pin "1") (pinfunction "1_1") (pintype "bidirectional"))
      (node (ref "C20") (pin "1") (pinfunction "1_1") (pintype "passive"))
      (node (ref "J3") (pin "1") (pinfunction "VBUS_1") (pintype "passive"))
      (node (ref "R18") (pin "1") (pinfunction "1_1") (pintype "passive"))
      (node (ref "U7") (pin "2") (pinfunction "VIN_2") (pintype "passive"))
      (node (ref "U7") (pin "3") (pinfunction "VIN_3") (pintype "passive"))
      (node (ref "VUSB") (pin "TP") (pinfunction "TP_TP") (pintype "input"))
    )
    (net (code "55") (name "unconnected-(J3-ID-Pad4)") (class "Default")
      (node (ref "J3") (pin "4") (pinfunction "ID_4") (pintype "passive"))
    )
    (net (code "56") (name "unconnected-(J4-KEY-Pad7)") (class "Default")
      (node (ref "J4") (pin "7") (pinfunction "KEY_7") (pintype "bidirectional"))
    )
    (net (code "57") (name "unconnected-(J4-NC{slash}TDI-Pad8)") (class "Default")
      (node (ref "J4") (pin "8") (pinfunction "NC/TDI_8") (pintype "bidirectional"))
    )
    (net (code "58") (name "unconnected-(J4-SWO{slash}TDO-Pad6)") (class "Default")
      (node (ref "J4") (pin "6") (pinfunction "SWO/TDO_6") (pintype "bidirectional"))
    )
    (net (code "59") (name "unconnected-(U$2-PCTLZ-Pad6)") (class "Default")
      (node (ref "U$2") (pin "6") (pinfunction "PCTLZ_6") (pintype "output"))
    )
    (net (code "60") (name "unconnected-(U$3-NC-Pad7)") (class "Default")
      (node (ref "U$3") (pin "7") (pinfunction "NC_7") (pintype "bidirectional"))
    )
    (net (code "61") (name "unconnected-(U$3-NC-Pad8)") (class "Default")
      (node (ref "U$3") (pin "8") (pinfunction "NC_8") (pintype "bidirectional"))
    )
    (net (code "62") (name "unconnected-(U$3-NC-Pad9)") (class "Default")
      (node (ref "U$3") (pin "9") (pinfunction "NC_9") (pintype "bidirectional"))
    )
    (net (code "63") (name "unconnected-(U$3-NC-Pad10)") (class "Default")
      (node (ref "U$3") (pin "10") (pinfunction "NC_10") (pintype "bidirectional"))
    )
    (net (code "64") (name "unconnected-(U$3-NC-Pad11)") (class "Default")
      (node (ref "U$3") (pin "11") (pinfunction "NC_11") (pintype "bidirectional"))
    )
    (net (code "65") (name "unconnected-(U$3-NC-Pad12)") (class "Default")
      (node (ref "U$3") (pin "12") (pinfunction "NC_12") (pintype "bidirectional"))
    )
    (net (code "66") (name "unconnected-(U$3-NC-Pad14)") (class "Default")
      (node (ref "U$3") (pin "14") (pinfunction "NC_14") (pintype "bidirectional"))
    )
    (net (code "67") (name "unconnected-(U$3-NC-Pad16)") (class "Default")
      (node (ref "U$3") (pin "16") (pinfunction "NC_16") (pintype "bidirectional"))
    )
    (net (code "68") (name "unconnected-(U$3-NC-Pad17)") (class "Default")
      (node (ref "U$3") (pin "17") (pinfunction "NC_17") (pintype "bidirectional"))
    )
    (net (code "69") (name "unconnected-(U$3-NC-Pad18)") (class "Default")
      (node (ref "U$3") (pin "18") (pinfunction "NC_18") (pintype "bidirectional"))
    )
    (net (code "70") (name "unconnected-(U$3-NC-Pad19)") (class "Default")
      (node (ref "U$3") (pin "19") (pinfunction "NC_19") (pintype "bidirectional"))
    )
    (net (code "71") (name "unconnected-(U$3-NC-Pad20)") (class "Default")
      (node (ref "U$3") (pin "20") (pinfunction "NC_20") (pintype "bidirectional"))
    )
    (net (code "72") (name "unconnected-(U$3-NC-Pad21)") (class "Default")
      (node (ref "U$3") (pin "21") (pinfunction "NC_21") (pintype "bidirectional"))
    )
    (net (code "73") (name "unconnected-(U$3-NC-Pad22)") (class "Default")
      (node (ref "U$3") (pin "22") (pinfunction "NC_22") (pintype "bidirectional"))
    )
    (net (code "74") (name "unconnected-(U$3-NC-Pad24)") (class "Default")
      (node (ref "U$3") (pin "24") (pinfunction "NC_24") (pintype "bidirectional"))
    )
    (net (code "75") (name "unconnected-(U$3-NC-Pad38)") (class "Default")
      (node (ref "U$3") (pin "38") (pinfunction "NC_38") (pintype "bidirectional"))
    )
    (net (code "76") (name "unconnected-(U$3-NC-Pad56)") (class "Default")
      (node (ref "U$3") (pin "56") (pinfunction "NC_56") (pintype "bidirectional"))
    )
    (net (code "77") (name "unconnected-(U$3-NC-Pad57)") (class "Default")
      (node (ref "U$3") (pin "57") (pinfunction "NC_57") (pintype "bidirectional"))
    )
    (net (code "78") (name "unconnected-(U$3-NC-Pad58)") (class "Default")
      (node (ref "U$3") (pin "58") (pinfunction "NC_58") (pintype "bidirectional"))
    )
    (net (code "79") (name "unconnected-(U$3-NC-Pad60)") (class "Default")
      (node (ref "U$3") (pin "60") (pinfunction "NC_60") (pintype "bidirectional"))
    )
    (net (code "80") (name "unconnected-(U1-INT-Pad3)") (class "Default")
      (node (ref "U1") (pin "3") (pinfunction "INT_3") (pintype "output"))
    )
    (net (code "81") (name "unconnected-(U2-INT-Pad3)") (class "Default")
      (node (ref "U2") (pin "3") (pinfunction "INT_3") (pintype "output"))
    )
    (net (code "82") (name "unconnected-(U5-{slash}IRQ3-Pad8)") (class "Default")
      (node (ref "U5") (pin "8") (pinfunction "/IRQ3_8") (pintype "output"))
    )
    (net (code "83") (name "unconnected-(U5-{slash}TIRQ-Pad12)") (class "Default")
      (node (ref "U5") (pin "12") (pinfunction "/TIRQ_12") (pintype "output"))
    )
    (net (code "84") (name "unconnected-(U6-DIO1-Pad7P)") (class "Default")
      (node (ref "U6") (pin "7P") (pinfunction "DIO1_7P") (pintype "bidirectional"))
    )
    (net (code "85") (name "unconnected-(U6-DIO2-Pad8P)") (class "Default")
      (node (ref "U6") (pin "8P") (pinfunction "DIO2_8P") (pintype "bidirectional"))
    )
    (net (code "86") (name "unconnected-(U6-DIO3-Pad3P)") (class "Default")
      (node (ref "U6") (pin "3P") (pinfunction "DIO3_3P") (pintype "bidirectional"))
    )
    (net (code "87") (name "unconnected-(U6-DIO4-Pad4P)") (class "Default")
      (node (ref "U6") (pin "4P") (pinfunction "DIO4_4P") (pintype "bidirectional"))
    )
    (net (code "88") (name "unconnected-(U6-DIO5-Pad15P)") (class "Default")
      (node (ref "U6") (pin "15P") (pinfunction "DIO5_15P") (pintype "bidirectional"))
    )
    (net (code "89") (name "{slash}IRQ2") (class "Default")
      (node (ref "Q4") (pin "1") (pinfunction "G_1") (pintype "bidirectional"))
      (node (ref "R7") (pin "1") (pinfunction "1_1") (pintype "passive"))
      (node (ref "U5") (pin "4") (pinfunction "/IRQ2_4") (pintype "output"))
    )
    (net (code "90") (name "{slash}RESET") (class "Default")
      (node (ref "R15") (pin "1") (pinfunction "1_1") (pintype "passive"))
      (node (ref "RESET") (pin "1") (pinfunction "P_1") (pintype "passive"))
      (node (ref "RESET") (pin "3") (pinfunction "P1_3") (pintype "passive"))
      (node (ref "U$3") (pin "34") (pinfunction "RST_34") (pintype "bidirectional"))
      (node (ref "U5") (pin "1") (pinfunction "/RST_1") (pintype "output"))
    )
    (net (code "91") (name "~{LORA_CS}") (class "Default")
      (node (ref "R12") (pin "2") (pinfunction "2_2") (pintype "passive"))
      (node (ref "U$3") (pin "52") (pinfunction "D4_52") (pintype "bidirectional"))
      (node (ref "U6") (pin "13P") (pinfunction "NSS_13P") (pintype "input"))
    )
    (net (code "92") (name "~{RESET}") (class "Default")
      (node (ref "!RESET") (pin "TP") (pinfunction "TP_TP") (pintype "input"))
      (node (ref "J4") (pin "10") (pinfunction "~{RESET}_10") (pintype "bidirectional"))
    )
  )
)
